# femto.net
KiCad netlist of a schematic drawn in EAGLE
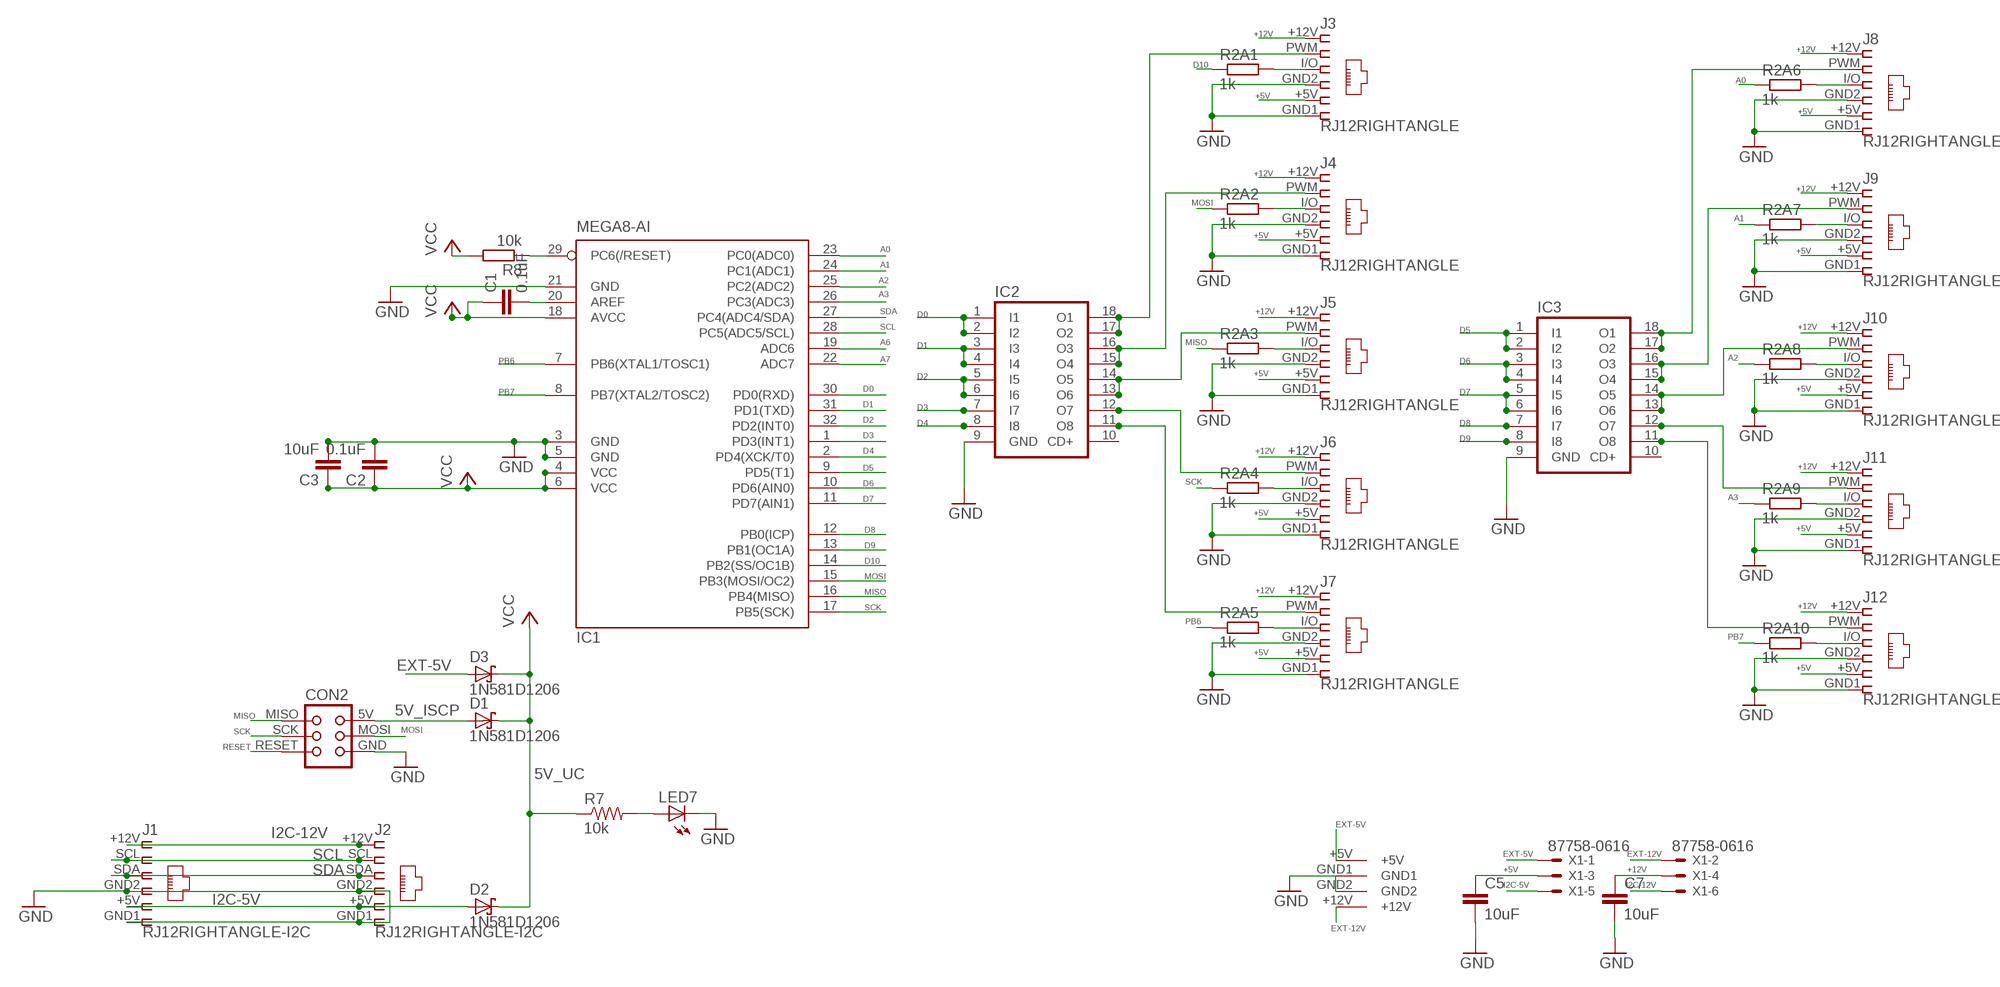
[diagram p0: schematic, sheet 1]

(export (version "E")
  (design (tool "Eeschema 10.0.6"))
  (components
    (comp (ref "C1")
      (value "0.1uF")
      (footprint "eagle-import:C1206")
      (libsource (lib "eagle-import") (part "resistor_C-EUC1206"))
    )
    (comp (ref "C2")
      (value "0.1uF")
      (footprint "eagle-import:C1206")
      (libsource (lib "eagle-import") (part "resistor_C-EUC1206"))
    )
    (comp (ref "C3")
      (value "10uF")
      (footprint "eagle-import:C1206")
      (libsource (lib "eagle-import") (part "resistor_C-EUC1206"))
    )
    (comp (ref "C5")
      (value "10uF")
      (footprint "eagle-import:C1206")
      (libsource (lib "eagle-import") (part "C-EUC1206"))
    )
    (comp (ref "C7")
      (value "10uF")
      (footprint "eagle-import:C1206")
      (libsource (lib "eagle-import") (part "C-EUC1206"))
    )
    (comp (ref "CON2")
      (value "TINYISPTAG")
      (footprint "eagle-import:TC2030-MCP")
      (libsource (lib "eagle-import") (part "TINYISPTAG"))
    )
    (comp (ref "D1")
      (value "1N581D1206")
      (footprint "eagle-import:LED-1206")
      (libsource (lib "eagle-import") (part "1N581D1206"))
    )
    (comp (ref "D2")
      (value "1N581D1206")
      (footprint "eagle-import:LED-1206")
      (libsource (lib "eagle-import") (part "1N581D1206"))
    )
    (comp (ref "D3")
      (value "1N581D1206")
      (footprint "eagle-import:LED-1206")
      (libsource (lib "eagle-import") (part "1N581D1206"))
    )
    (comp (ref "IC1")
      (value "MEGA8-AI")
      (footprint "eagle-import:TQFP32-08")
      (fields (field (name "MPN") "ATMEGA8-16AU"))
      (libsource (lib "eagle-import") (part "MEGA8-AI"))
    )
    (comp (ref "IC2")
      (value "ULN2803A")
      (footprint "eagle-import:SO18W")
      (libsource (lib "eagle-import") (part "ULN2803A"))
    )
    (comp (ref "IC3")
      (value "ULN2803A")
      (footprint "eagle-import:SO18W")
      (libsource (lib "eagle-import") (part "ULN2803A"))
    )
    (comp (ref "J1")
      (value "RJ12RIGHTANGLE-I2C")
      (footprint "eagle-import:RJ12-RIGHTANGLE-I2C")
      (libsource (lib "eagle-import") (part "RJ12RIGHTANGLE-I2C"))
    )
    (comp (ref "J2")
      (value "RJ12RIGHTANGLE-I2C")
      (footprint "eagle-import:RJ12-RIGHTANGLE-I2C")
      (libsource (lib "eagle-import") (part "RJ12RIGHTANGLE-I2C"))
    )
    (comp (ref "J3")
      (value "RJ12RIGHTANGLE")
      (footprint "eagle-import:RJ12-RIGHTANGLE")
      (libsource (lib "eagle-import") (part "RJ12RIGHTANGLE"))
    )
    (comp (ref "J4")
      (value "RJ12RIGHTANGLE")
      (footprint "eagle-import:RJ12-RIGHTANGLE")
      (libsource (lib "eagle-import") (part "RJ12RIGHTANGLE"))
    )
    (comp (ref "J5")
      (value "RJ12RIGHTANGLE")
      (footprint "eagle-import:RJ12-RIGHTANGLE")
      (libsource (lib "eagle-import") (part "RJ12RIGHTANGLE"))
    )
    (comp (ref "J6")
      (value "RJ12RIGHTANGLE")
      (footprint "eagle-import:RJ12-RIGHTANGLE")
      (libsource (lib "eagle-import") (part "RJ12RIGHTANGLE"))
    )
    (comp (ref "J7")
      (value "RJ12RIGHTANGLE")
      (footprint "eagle-import:RJ12-RIGHTANGLE")
      (libsource (lib "eagle-import") (part "RJ12RIGHTANGLE"))
    )
    (comp (ref "J8")
      (value "RJ12RIGHTANGLE")
      (footprint "eagle-import:RJ12-RIGHTANGLE")
      (libsource (lib "eagle-import") (part "RJ12RIGHTANGLE"))
    )
    (comp (ref "J9")
      (value "RJ12RIGHTANGLE")
      (footprint "eagle-import:RJ12-RIGHTANGLE")
      (libsource (lib "eagle-import") (part "RJ12RIGHTANGLE"))
    )
    (comp (ref "J10")
      (value "RJ12RIGHTANGLE")
      (footprint "eagle-import:RJ12-RIGHTANGLE")
      (libsource (lib "eagle-import") (part "RJ12RIGHTANGLE"))
    )
    (comp (ref "J11")
      (value "RJ12RIGHTANGLE")
      (footprint "eagle-import:RJ12-RIGHTANGLE")
      (libsource (lib "eagle-import") (part "RJ12RIGHTANGLE"))
    )
    (comp (ref "J12")
      (value "RJ12RIGHTANGLE")
      (footprint "eagle-import:RJ12-RIGHTANGLE")
      (libsource (lib "eagle-import") (part "RJ12RIGHTANGLE"))
    )
    (comp (ref "LED7")
      (value "LEDCHIP-LED0603")
      (footprint "eagle-import:CHIP-LED0603")
      (libsource (lib "eagle-import") (part "LEDCHIP-LED0603"))
    )
    (comp (ref "R2A1")
      (value "1k")
      (footprint "eagle-import:M1206")
      (libsource (lib "eagle-import") (part "R-EU_M1206"))
    )
    (comp (ref "R2A2")
      (value "1k")
      (footprint "eagle-import:M1206")
      (libsource (lib "eagle-import") (part "R-EU_M1206"))
    )
    (comp (ref "R2A3")
      (value "1k")
      (footprint "eagle-import:M1206")
      (libsource (lib "eagle-import") (part "R-EU_M1206"))
    )
    (comp (ref "R2A4")
      (value "1k")
      (footprint "eagle-import:M1206")
      (libsource (lib "eagle-import") (part "R-EU_M1206"))
    )
    (comp (ref "R2A5")
      (value "1k")
      (footprint "eagle-import:M1206")
      (libsource (lib "eagle-import") (part "R-EU_M1206"))
    )
    (comp (ref "R2A6")
      (value "1k")
      (footprint "eagle-import:M1206")
      (libsource (lib "eagle-import") (part "R-EU_M1206"))
    )
    (comp (ref "R2A7")
      (value "1k")
      (footprint "eagle-import:M1206")
      (libsource (lib "eagle-import") (part "R-EU_M1206"))
    )
    (comp (ref "R2A8")
      (value "1k")
      (footprint "eagle-import:M1206")
      (libsource (lib "eagle-import") (part "R-EU_M1206"))
    )
    (comp (ref "R2A9")
      (value "1k")
      (footprint "eagle-import:M1206")
      (libsource (lib "eagle-import") (part "R-EU_M1206"))
    )
    (comp (ref "R2A10")
      (value "1k")
      (footprint "eagle-import:M1206")
      (libsource (lib "eagle-import") (part "R-EU_M1206"))
    )
    (comp (ref "R7")
      (value "10k")
      (footprint "eagle-import:0603-RES")
      (libsource (lib "eagle-import") (part "RESISTOR0603-RES"))
    )
    (comp (ref "R8")
      (value "10k")
      (footprint "eagle-import:M1206")
      (libsource (lib "eagle-import") (part "R-EU_M1206"))
    )
    (comp (ref "U$1")
      (value "KPJX-4S-S")
      (footprint "eagle-import:KPJX-4S-S")
      (libsource (lib "eagle-import") (part "KPJX-4S-S"))
    )
    (comp (ref "X1")
      (value "87758-0616")
      (footprint "eagle-import:87758-0616")
      (libsource (lib "eagle-import") (part "87758-0616"))
    )
  )
  (nets
    (net (code "1") (name "/+5V") (class "Default")
      (node (ref "C5") (pin "1") (pinfunction "1_1") (pintype "passive"))
      (node (ref "J10") (pin "+5V") (pinfunction "5_+5V") (pintype "bidirectional"))
      (node (ref "J11") (pin "+5V") (pinfunction "5_+5V") (pintype "bidirectional"))
      (node (ref "J12") (pin "+5V") (pinfunction "5_+5V") (pintype "bidirectional"))
      (node (ref "J3") (pin "+5V") (pinfunction "5_+5V") (pintype "bidirectional"))
      (node (ref "J4") (pin "+5V") (pinfunction "5_+5V") (pintype "bidirectional"))
      (node (ref "J5") (pin "+5V") (pinfunction "5_+5V") (pintype "bidirectional"))
      (node (ref "J6") (pin "+5V") (pinfunction "5_+5V") (pintype "bidirectional"))
      (node (ref "J7") (pin "+5V") (pinfunction "5_+5V") (pintype "bidirectional"))
      (node (ref "J8") (pin "+5V") (pinfunction "5_+5V") (pintype "bidirectional"))
      (node (ref "J9") (pin "+5V") (pinfunction "5_+5V") (pintype "bidirectional"))
      (node (ref "X1") (pin "3") (pinfunction "S_3") (pintype "passive"))
    )
    (net (code "2") (name "/+12V") (class "Default")
      (node (ref "C7") (pin "1") (pinfunction "1_1") (pintype "passive"))
      (node (ref "J10") (pin "+12V") (pinfunction "1_+12V") (pintype "bidirectional"))
      (node (ref "J11") (pin "+12V") (pinfunction "1_+12V") (pintype "bidirectional"))
      (node (ref "J12") (pin "+12V") (pinfunction "1_+12V") (pintype "bidirectional"))
      (node (ref "J3") (pin "+12V") (pinfunction "1_+12V") (pintype "bidirectional"))
      (node (ref "J4") (pin "+12V") (pinfunction "1_+12V") (pintype "bidirectional"))
      (node (ref "J5") (pin "+12V") (pinfunction "1_+12V") (pintype "bidirectional"))
      (node (ref "J6") (pin "+12V") (pinfunction "1_+12V") (pintype "bidirectional"))
      (node (ref "J7") (pin "+12V") (pinfunction "1_+12V") (pintype "bidirectional"))
      (node (ref "J8") (pin "+12V") (pinfunction "1_+12V") (pintype "bidirectional"))
      (node (ref "J9") (pin "+12V") (pinfunction "1_+12V") (pintype "bidirectional"))
      (node (ref "X1") (pin "4") (pinfunction "S_4") (pintype "passive"))
    )
    (net (code "3") (name "/5V_ISCP") (class "Default")
      (node (ref "CON2") (pin "5V") (pinfunction "VCC_5V") (pintype "passive"))
      (node (ref "D1") (pin "A") (pinfunction "A_A") (pintype "passive"))
    )
    (net (code "4") (name "/A0") (class "Default")
      (node (ref "IC1") (pin "23") (pinfunction "PC0(ADC0)_23") (pintype "bidirectional"))
      (node (ref "R2A6") (pin "1") (pinfunction "1_1") (pintype "passive"))
    )
    (net (code "5") (name "/A1") (class "Default")
      (node (ref "IC1") (pin "24") (pinfunction "PC1(ADC1)_24") (pintype "bidirectional"))
      (node (ref "R2A7") (pin "1") (pinfunction "1_1") (pintype "passive"))
    )
    (net (code "6") (name "/A2") (class "Default")
      (node (ref "IC1") (pin "25") (pinfunction "PC2(ADC2)_25") (pintype "bidirectional"))
      (node (ref "R2A8") (pin "1") (pinfunction "1_1") (pintype "passive"))
    )
    (net (code "7") (name "/A3") (class "Default")
      (node (ref "IC1") (pin "26") (pinfunction "PC3(ADC3)_26") (pintype "bidirectional"))
      (node (ref "R2A9") (pin "1") (pinfunction "1_1") (pintype "passive"))
    )
    (net (code "8") (name "/A6") (class "Default")
      (node (ref "IC1") (pin "19") (pinfunction "ADC6_19") (pintype "bidirectional"))
    )
    (net (code "9") (name "/A7") (class "Default")
      (node (ref "IC1") (pin "22") (pinfunction "ADC7_22") (pintype "bidirectional"))
    )
    (net (code "10") (name "/D0") (class "Default")
      (node (ref "IC1") (pin "30") (pinfunction "PD0(RXD)_30") (pintype "bidirectional"))
      (node (ref "IC2") (pin "1") (pinfunction "I1_1") (pintype "input"))
      (node (ref "IC2") (pin "2") (pinfunction "I2_2") (pintype "input"))
    )
    (net (code "11") (name "/D1") (class "Default")
      (node (ref "IC1") (pin "31") (pinfunction "PD1(TXD)_31") (pintype "bidirectional"))
      (node (ref "IC2") (pin "3") (pinfunction "I3_3") (pintype "input"))
      (node (ref "IC2") (pin "4") (pinfunction "I4_4") (pintype "input"))
    )
    (net (code "12") (name "/D2") (class "Default")
      (node (ref "IC1") (pin "32") (pinfunction "PD2(INT0)_32") (pintype "bidirectional"))
      (node (ref "IC2") (pin "5") (pinfunction "I5_5") (pintype "input"))
      (node (ref "IC2") (pin "6") (pinfunction "I6_6") (pintype "input"))
    )
    (net (code "13") (name "/D3") (class "Default")
      (node (ref "IC1") (pin "1") (pinfunction "PD3(INT1)_1") (pintype "bidirectional"))
      (node (ref "IC2") (pin "7") (pinfunction "I7_7") (pintype "input"))
    )
    (net (code "14") (name "/D4") (class "Default")
      (node (ref "IC1") (pin "2") (pinfunction "PD4(XCK/T0)_2") (pintype "bidirectional"))
      (node (ref "IC2") (pin "8") (pinfunction "I8_8") (pintype "input"))
    )
    (net (code "15") (name "/D5") (class "Default")
      (node (ref "IC1") (pin "9") (pinfunction "PD5(T1)_9") (pintype "bidirectional"))
      (node (ref "IC3") (pin "1") (pinfunction "I1_1") (pintype "input"))
      (node (ref "IC3") (pin "2") (pinfunction "I2_2") (pintype "input"))
    )
    (net (code "16") (name "/D6") (class "Default")
      (node (ref "IC1") (pin "10") (pinfunction "PD6(AIN0)_10") (pintype "bidirectional"))
      (node (ref "IC3") (pin "3") (pinfunction "I3_3") (pintype "input"))
      (node (ref "IC3") (pin "4") (pinfunction "I4_4") (pintype "input"))
    )
    (net (code "17") (name "/D7") (class "Default")
      (node (ref "IC1") (pin "11") (pinfunction "PD7(AIN1)_11") (pintype "bidirectional"))
      (node (ref "IC3") (pin "5") (pinfunction "I5_5") (pintype "input"))
      (node (ref "IC3") (pin "6") (pinfunction "I6_6") (pintype "input"))
    )
    (net (code "18") (name "/D8") (class "Default")
      (node (ref "IC1") (pin "12") (pinfunction "PB0(ICP)_12") (pintype "bidirectional"))
      (node (ref "IC3") (pin "7") (pinfunction "I7_7") (pintype "input"))
    )
    (net (code "19") (name "/D9") (class "Default")
      (node (ref "IC1") (pin "13") (pinfunction "PB1(OC1A)_13") (pintype "bidirectional"))
      (node (ref "IC3") (pin "8") (pinfunction "I8_8") (pintype "input"))
    )
    (net (code "20") (name "/D10") (class "Default")
      (node (ref "IC1") (pin "14") (pinfunction "PB2(SS/OC1B)_14") (pintype "bidirectional"))
      (node (ref "R2A1") (pin "1") (pinfunction "1_1") (pintype "passive"))
    )
    (net (code "21") (name "/EXT-5V") (class "Default")
      (node (ref "D3") (pin "A") (pinfunction "A_A") (pintype "passive"))
      (node (ref "U$1") (pin "+5V") (pinfunction "+5V_+5V") (pintype "power_in"))
      (node (ref "X1") (pin "1") (pinfunction "S_1") (pintype "passive"))
    )
    (net (code "22") (name "/EXT-12V") (class "Default")
      (node (ref "U$1") (pin "+12V") (pinfunction "+12V_+12V") (pintype "power_in"))
      (node (ref "X1") (pin "2") (pinfunction "S_2") (pintype "passive"))
    )
    (net (code "23") (name "/I2C-5V") (class "Default")
      (node (ref "D2") (pin "A") (pinfunction "A_A") (pintype "passive"))
      (node (ref "J1") (pin "+5V") (pinfunction "5_+5V") (pintype "bidirectional"))
      (node (ref "J2") (pin "+5V") (pinfunction "5_+5V") (pintype "bidirectional"))
      (node (ref "X1") (pin "5") (pinfunction "S_5") (pintype "passive"))
    )
    (net (code "24") (name "/I2C-12V") (class "Default")
      (node (ref "J1") (pin "+12V") (pinfunction "1_+12V") (pintype "bidirectional"))
      (node (ref "J2") (pin "+12V") (pinfunction "1_+12V") (pintype "bidirectional"))
      (node (ref "X1") (pin "6") (pinfunction "S_6") (pintype "passive"))
    )
    (net (code "25") (name "/MISO") (class "Default")
      (node (ref "CON2") (pin "MISO") (pinfunction "MISO_MISO") (pintype "passive"))
      (node (ref "IC1") (pin "16") (pinfunction "PB4(MISO)_16") (pintype "bidirectional"))
      (node (ref "R2A3") (pin "1") (pinfunction "1_1") (pintype "passive"))
    )
    (net (code "26") (name "/MOSI") (class "Default")
      (node (ref "CON2") (pin "MOSI") (pinfunction "MOSI_MOSI") (pintype "passive"))
      (node (ref "IC1") (pin "15") (pinfunction "PB3(MOSI/OC2)_15") (pintype "bidirectional"))
      (node (ref "R2A2") (pin "1") (pinfunction "1_1") (pintype "passive"))
    )
    (net (code "27") (name "/PB6") (class "Default")
      (node (ref "IC1") (pin "7") (pinfunction "PB6(XTAL1/TOSC1)_7") (pintype "bidirectional"))
      (node (ref "R2A5") (pin "1") (pinfunction "1_1") (pintype "passive"))
    )
    (net (code "28") (name "/PB7") (class "Default")
      (node (ref "IC1") (pin "8") (pinfunction "PB7(XTAL2/TOSC2)_8") (pintype "bidirectional"))
      (node (ref "R2A10") (pin "1") (pinfunction "1_1") (pintype "passive"))
    )
    (net (code "29") (name "/RESET") (class "Default")
      (node (ref "CON2") (pin "RESET") (pinfunction "RESET_RESET") (pintype "passive"))
      (node (ref "IC1") (pin "29") (pinfunction "PC6(/RESET)_29") (pintype "bidirectional"))
      (node (ref "R8") (pin "1") (pinfunction "1_1") (pintype "passive"))
    )
    (net (code "30") (name "/SCK") (class "Default")
      (node (ref "CON2") (pin "SCK") (pinfunction "SCK_SCK") (pintype "passive"))
      (node (ref "IC1") (pin "17") (pinfunction "PB5(SCK)_17") (pintype "bidirectional"))
      (node (ref "R2A4") (pin "1") (pinfunction "1_1") (pintype "passive"))
    )
    (net (code "31") (name "/SCL") (class "Default")
      (node (ref "IC1") (pin "28") (pinfunction "PC5(ADC5/SCL)_28") (pintype "bidirectional"))
      (node (ref "J1") (pin "SCL") (pinfunction "2_SCL") (pintype "bidirectional"))
      (node (ref "J2") (pin "SCL") (pinfunction "2_SCL") (pintype "bidirectional"))
    )
    (net (code "32") (name "/SDA") (class "Default")
      (node (ref "IC1") (pin "27") (pinfunction "PC4(ADC4/SDA)_27") (pintype "bidirectional"))
      (node (ref "J1") (pin "SDA") (pinfunction "3_SDA") (pintype "bidirectional"))
      (node (ref "J2") (pin "SDA") (pinfunction "3_SDA") (pintype "bidirectional"))
    )
    (net (code "33") (name "GND") (class "Default")
      (node (ref "C2") (pin "2") (pinfunction "2_2") (pintype "passive"))
      (node (ref "C3") (pin "2") (pinfunction "2_2") (pintype "passive"))
      (node (ref "C5") (pin "2") (pinfunction "2_2") (pintype "passive"))
      (node (ref "C7") (pin "2") (pinfunction "2_2") (pintype "passive"))
      (node (ref "CON2") (pin "GND") (pinfunction "GND_GND") (pintype "passive"))
      (node (ref "IC1") (pin "21") (pinfunction "GND_21") (pintype "power_in"))
      (node (ref "IC1") (pin "3") (pinfunction "GND_3") (pintype "power_in"))
      (node (ref "IC1") (pin "5") (pinfunction "GND_5") (pintype "power_in"))
      (node (ref "IC2") (pin "9") (pinfunction "GND_9") (pintype "power_in"))
      (node (ref "IC3") (pin "9") (pinfunction "GND_9") (pintype "power_in"))
      (node (ref "J1") (pin "GND1") (pinfunction "6_GND1") (pintype "bidirectional"))
      (node (ref "J1") (pin "GND2") (pinfunction "4_GND2") (pintype "bidirectional"))
      (node (ref "J10") (pin "GND1") (pinfunction "6_GND1") (pintype "bidirectional"))
      (node (ref "J10") (pin "GND2") (pinfunction "4_GND2") (pintype "bidirectional"))
      (node (ref "J11") (pin "GND1") (pinfunction "6_GND1") (pintype "bidirectional"))
      (node (ref "J11") (pin "GND2") (pinfunction "4_GND2") (pintype "bidirectional"))
      (node (ref "J12") (pin "GND1") (pinfunction "6_GND1") (pintype "bidirectional"))
      (node (ref "J12") (pin "GND2") (pinfunction "4_GND2") (pintype "bidirectional"))
      (node (ref "J2") (pin "GND1") (pinfunction "6_GND1") (pintype "bidirectional"))
      (node (ref "J2") (pin "GND2") (pinfunction "4_GND2") (pintype "bidirectional"))
      (node (ref "J3") (pin "GND1") (pinfunction "6_GND1") (pintype "bidirectional"))
      (node (ref "J3") (pin "GND2") (pinfunction "4_GND2") (pintype "bidirectional"))
      (node (ref "J4") (pin "GND1") (pinfunction "6_GND1") (pintype "bidirectional"))
      (node (ref "J4") (pin "GND2") (pinfunction "4_GND2") (pintype "bidirectional"))
      (node (ref "J5") (pin "GND1") (pinfunction "6_GND1") (pintype "bidirectional"))
      (node (ref "J5") (pin "GND2") (pinfunction "4_GND2") (pintype "bidirectional"))
      (node (ref "J6") (pin "GND1") (pinfunction "6_GND1") (pintype "bidirectional"))
      (node (ref "J6") (pin "GND2") (pinfunction "4_GND2") (pintype "bidirectional"))
      (node (ref "J7") (pin "GND1") (pinfunction "6_GND1") (pintype "bidirectional"))
      (node (ref "J7") (pin "GND2") (pinfunction "4_GND2") (pintype "bidirectional"))
      (node (ref "J8") (pin "GND1") (pinfunction "6_GND1") (pintype "bidirectional"))
      (node (ref "J8") (pin "GND2") (pinfunction "4_GND2") (pintype "bidirectional"))
      (node (ref "J9") (pin "GND1") (pinfunction "6_GND1") (pintype "bidirectional"))
      (node (ref "J9") (pin "GND2") (pinfunction "4_GND2") (pintype "bidirectional"))
      (node (ref "LED7") (pin "C") (pinfunction "C_C") (pintype "passive"))
      (node (ref "U$1") (pin "GND1") (pinfunction "GND1_GND1") (pintype "input"))
      (node (ref "U$1") (pin "GND2") (pinfunction "GND2_GND2") (pintype "input"))
    )
    (net (code "34") (name "Net-(IC1-AREF)") (class "Default")
      (node (ref "C1") (pin "2") (pinfunction "2_2") (pintype "passive"))
      (node (ref "IC1") (pin "20") (pinfunction "AREF_20") (pintype "passive"))
    )
    (net (code "35") (name "Net-(IC2-O1)") (class "Default")
      (node (ref "IC2") (pin "17") (pinfunction "O2_17") (pintype "open_collector"))
      (node (ref "IC2") (pin "18") (pinfunction "O1_18") (pintype "open_collector"))
      (node (ref "J3") (pin "PWM") (pinfunction "2_PWM") (pintype "bidirectional"))
    )
    (net (code "36") (name "Net-(IC2-O3)") (class "Default")
      (node (ref "IC2") (pin "15") (pinfunction "O4_15") (pintype "open_collector"))
      (node (ref "IC2") (pin "16") (pinfunction "O3_16") (pintype "open_collector"))
      (node (ref "J4") (pin "PWM") (pinfunction "2_PWM") (pintype "bidirectional"))
    )
    (net (code "37") (name "Net-(IC2-O5)") (class "Default")
      (node (ref "IC2") (pin "13") (pinfunction "O6_13") (pintype "open_collector"))
      (node (ref "IC2") (pin "14") (pinfunction "O5_14") (pintype "open_collector"))
      (node (ref "J5") (pin "PWM") (pinfunction "2_PWM") (pintype "bidirectional"))
    )
    (net (code "38") (name "Net-(IC2-O7)") (class "Default")
      (node (ref "IC2") (pin "12") (pinfunction "O7_12") (pintype "open_collector"))
      (node (ref "J6") (pin "PWM") (pinfunction "2_PWM") (pintype "bidirectional"))
    )
    (net (code "39") (name "Net-(IC2-O8)") (class "Default")
      (node (ref "IC2") (pin "11") (pinfunction "O8_11") (pintype "open_collector"))
      (node (ref "J7") (pin "PWM") (pinfunction "2_PWM") (pintype "bidirectional"))
    )
    (net (code "40") (name "Net-(IC3-O1)") (class "Default")
      (node (ref "IC3") (pin "17") (pinfunction "O2_17") (pintype "open_collector"))
      (node (ref "IC3") (pin "18") (pinfunction "O1_18") (pintype "open_collector"))
      (node (ref "J8") (pin "PWM") (pinfunction "2_PWM") (pintype "bidirectional"))
    )
    (net (code "41") (name "Net-(IC3-O3)") (class "Default")
      (node (ref "IC3") (pin "15") (pinfunction "O4_15") (pintype "open_collector"))
      (node (ref "IC3") (pin "16") (pinfunction "O3_16") (pintype "open_collector"))
      (node (ref "J9") (pin "PWM") (pinfunction "2_PWM") (pintype "bidirectional"))
    )
    (net (code "42") (name "Net-(IC3-O5)") (class "Default")
      (node (ref "IC3") (pin "13") (pinfunction "O6_13") (pintype "open_collector"))
      (node (ref "IC3") (pin "14") (pinfunction "O5_14") (pintype "open_collector"))
      (node (ref "J10") (pin "PWM") (pinfunction "2_PWM") (pintype "bidirectional"))
    )
    (net (code "43") (name "Net-(IC3-O7)") (class "Default")
      (node (ref "IC3") (pin "12") (pinfunction "O7_12") (pintype "open_collector"))
      (node (ref "J11") (pin "PWM") (pinfunction "2_PWM") (pintype "bidirectional"))
    )
    (net (code "44") (name "Net-(IC3-O8)") (class "Default")
      (node (ref "IC3") (pin "11") (pinfunction "O8_11") (pintype "open_collector"))
      (node (ref "J12") (pin "PWM") (pinfunction "2_PWM") (pintype "bidirectional"))
    )
    (net (code "45") (name "Net-(J3-3)") (class "Default")
      (node (ref "J3") (pin "I/O") (pinfunction "3_I/O") (pintype "bidirectional"))
      (node (ref "R2A1") (pin "2") (pinfunction "2_2") (pintype "passive"))
    )
    (net (code "46") (name "Net-(J4-3)") (class "Default")
      (node (ref "J4") (pin "I/O") (pinfunction "3_I/O") (pintype "bidirectional"))
      (node (ref "R2A2") (pin "2") (pinfunction "2_2") (pintype "passive"))
    )
    (net (code "47") (name "Net-(J5-3)") (class "Default")
      (node (ref "J5") (pin "I/O") (pinfunction "3_I/O") (pintype "bidirectional"))
      (node (ref "R2A3") (pin "2") (pinfunction "2_2") (pintype "passive"))
    )
    (net (code "48") (name "Net-(J6-3)") (class "Default")
      (node (ref "J6") (pin "I/O") (pinfunction "3_I/O") (pintype "bidirectional"))
      (node (ref "R2A4") (pin "2") (pinfunction "2_2") (pintype "passive"))
    )
    (net (code "49") (name "Net-(J7-3)") (class "Default")
      (node (ref "J7") (pin "I/O") (pinfunction "3_I/O") (pintype "bidirectional"))
      (node (ref "R2A5") (pin "2") (pinfunction "2_2") (pintype "passive"))
    )
    (net (code "50") (name "Net-(J8-3)") (class "Default")
      (node (ref "J8") (pin "I/O") (pinfunction "3_I/O") (pintype "bidirectional"))
      (node (ref "R2A6") (pin "2") (pinfunction "2_2") (pintype "passive"))
    )
    (net (code "51") (name "Net-(J9-3)") (class "Default")
      (node (ref "J9") (pin "I/O") (pinfunction "3_I/O") (pintype "bidirectional"))
      (node (ref "R2A7") (pin "2") (pinfunction "2_2") (pintype "passive"))
    )
    (net (code "52") (name "Net-(J10-3)") (class "Default")
      (node (ref "J10") (pin "I/O") (pinfunction "3_I/O") (pintype "bidirectional"))
      (node (ref "R2A8") (pin "2") (pinfunction "2_2") (pintype "passive"))
    )
    (net (code "53") (name "Net-(J11-3)") (class "Default")
      (node (ref "J11") (pin "I/O") (pinfunction "3_I/O") (pintype "bidirectional"))
      (node (ref "R2A9") (pin "2") (pinfunction "2_2") (pintype "passive"))
    )
    (net (code "54") (name "Net-(J12-3)") (class "Default")
      (node (ref "J12") (pin "I/O") (pinfunction "3_I/O") (pintype "bidirectional"))
      (node (ref "R2A10") (pin "2") (pinfunction "2_2") (pintype "passive"))
    )
    (net (code "55") (name "Net-(LED7-PadA)") (class "Default")
      (node (ref "LED7") (pin "A") (pinfunction "A_A") (pintype "passive"))
      (node (ref "R7") (pin "2") (pinfunction "2_2") (pintype "passive"))
    )
    (net (code "56") (name "VCC") (class "Default")
      (node (ref "C1") (pin "1") (pinfunction "1_1") (pintype "passive"))
      (node (ref "C2") (pin "1") (pinfunction "1_1") (pintype "passive"))
      (node (ref "C3") (pin "1") (pinfunction "1_1") (pintype "passive"))
      (node (ref "D1") (pin "C") (pinfunction "C_C") (pintype "passive"))
      (node (ref "D2") (pin "C") (pinfunction "C_C") (pintype "passive"))
      (node (ref "D3") (pin "C") (pinfunction "C_C") (pintype "passive"))
      (node (ref "IC1") (pin "18") (pinfunction "AVCC_18") (pintype "power_in"))
      (node (ref "IC1") (pin "4") (pinfunction "VCC_4") (pintype "power_in"))
      (node (ref "IC1") (pin "6") (pinfunction "VCC_6") (pintype "power_in"))
      (node (ref "R7") (pin "1") (pinfunction "1_1") (pintype "passive"))
      (node (ref "R8") (pin "2") (pinfunction "2_2") (pintype "passive"))
    )
    (net (code "57") (name "unconnected-(IC2-CD+-Pad10)") (class "Default")
      (node (ref "IC2") (pin "10") (pinfunction "CD+_10") (pintype "passive"))
    )
    (net (code "58") (name "unconnected-(IC3-CD+-Pad10)") (class "Default")
      (node (ref "IC3") (pin "10") (pinfunction "CD+_10") (pintype "passive"))
    )
  )
)
